# Sheet1.net
KiCad netlist of a schematic drawn in Altium Designer
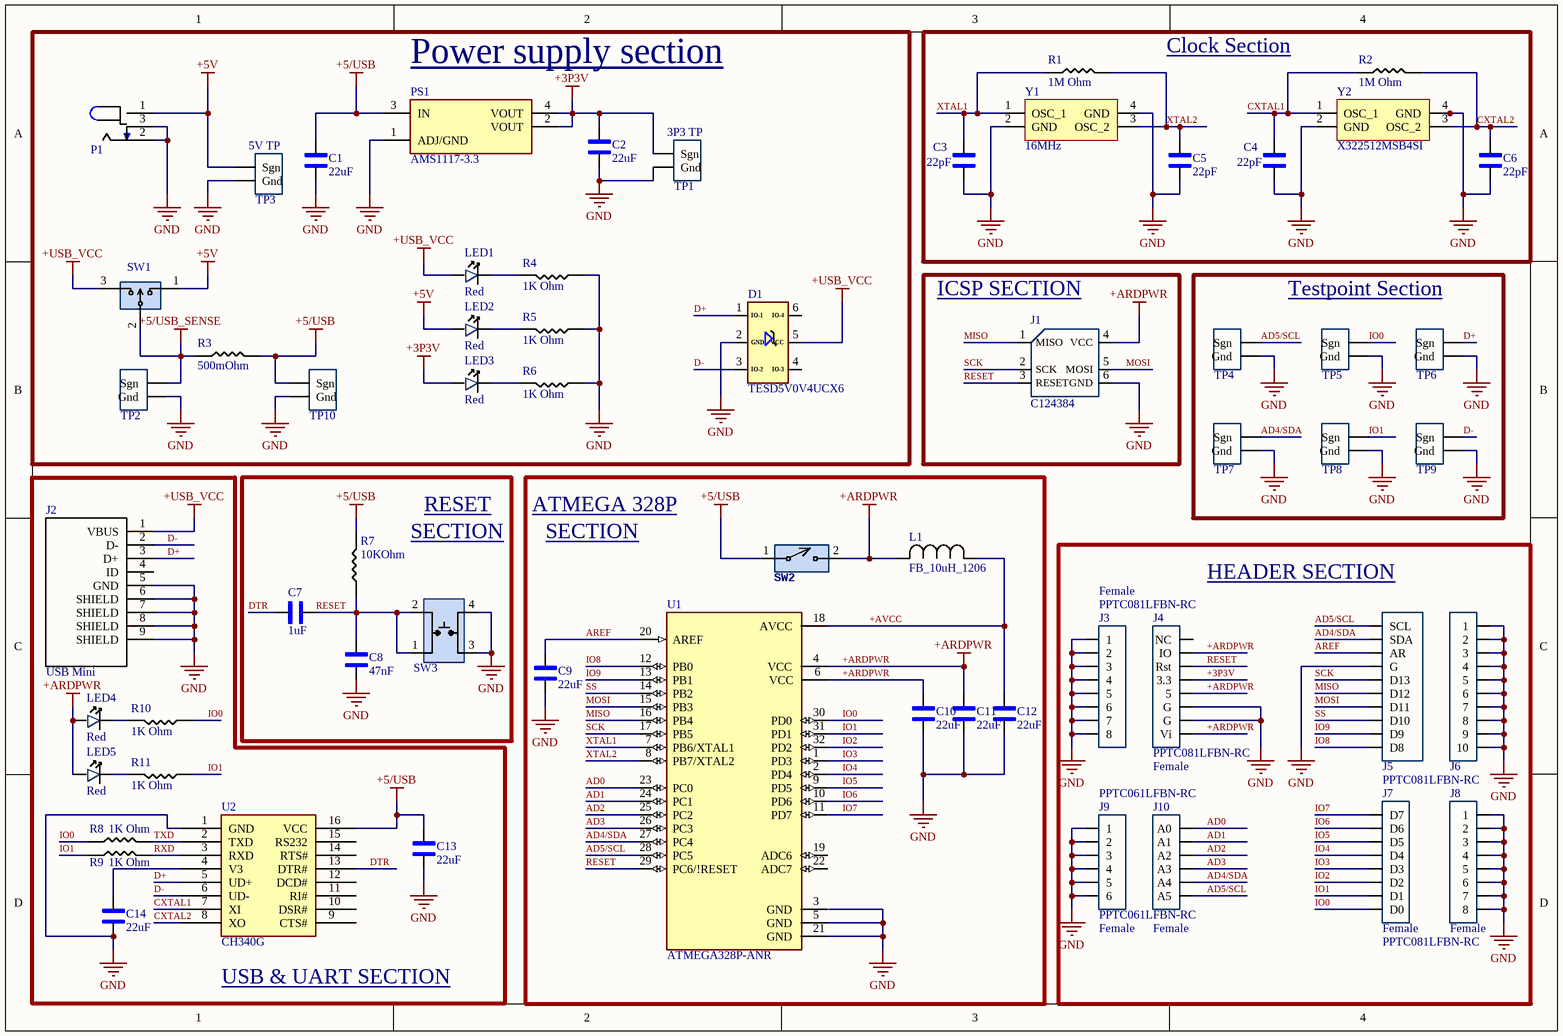
[diagram p0: Sheet1.SchDoc]

(export (version "E")
  (design (tool "Eeschema 10.0.6"))
  (components
    (comp (ref "C1")
      (value "22uF")
      (footprint "1206_Passive_Capacitor")
      (description "22uF ±10% 25V X5R 1206 Multilayer Ceramic Capacitors MLCC - SMD/SMT RoHS")
      (fields (field (name "MFR PART #") "CL31A226KAHNNNE") (field (name "LCSC PART#") "C12891"))
      (libsource (lib "ECEN5730Lib_2023_05_DS (1)") (part "C_22uF_1206"))
    )
    (comp (ref "C2")
      (value "22uF")
      (footprint "1206_Passive_Capacitor")
      (description "22uF ±10% 25V X5R 1206 Multilayer Ceramic Capacitors MLCC - SMD/SMT RoHS")
      (fields (field (name "MFR PART #") "CL31A226KAHNNNE") (field (name "LCSC PART#") "C12891"))
      (libsource (lib "ECEN5730Lib_2023_05_DS (1)") (part "C_22uF_1206"))
    )
    (comp (ref "C3")
      (value "22pF")
      (footprint "1206_Passive_Capacitor")
      (description "22pF ±5% 1kV C0G 1206 Multilayer Ceramic Capacitors MLCC - SMD/SMT RoHS")
      (fields (field (name "LCSC PART#") "C107174") (field (name "MFR PART #") "CC1206JKNPOCBN220"))
      (libsource (lib "ECEN5730Lib_2023_05_DS (1)") (part "C_22pF_1206"))
    )
    (comp (ref "C4")
      (value "22pF")
      (footprint "1206_Passive_Capacitor")
      (description "22pF ±5% 1kV C0G 1206 Multilayer Ceramic Capacitors MLCC - SMD/SMT RoHS")
      (fields (field (name "LCSC PART#") "C107174") (field (name "MFR PART #") "CC1206JKNPOCBN220"))
      (libsource (lib "ECEN5730Lib_2023_05_DS (1)") (part "C_22pF_1206"))
    )
    (comp (ref "C5")
      (value "22pF")
      (footprint "1206_Passive_Capacitor")
      (description "22pF ±5% 1kV C0G 1206 Multilayer Ceramic Capacitors MLCC - SMD/SMT RoHS")
      (fields (field (name "LCSC PART#") "C107174") (field (name "MFR PART #") "CC1206JKNPOCBN220"))
      (libsource (lib "ECEN5730Lib_2023_05_DS (1)") (part "C_22pF_1206"))
    )
    (comp (ref "C6")
      (value "22pF")
      (footprint "1206_Passive_Capacitor")
      (description "22pF ±5% 1kV C0G 1206 Multilayer Ceramic Capacitors MLCC - SMD/SMT RoHS")
      (fields (field (name "LCSC PART#") "C107174") (field (name "MFR PART #") "CC1206JKNPOCBN220"))
      (libsource (lib "ECEN5730Lib_2023_05_DS (1)") (part "C_22pF_1206"))
    )
    (comp (ref "C7")
      (value "1uF")
      (footprint "1206_Passive_Capacitor")
      (description "MULTILAYER CERAMIC CAPACITORS MLCC - SMD/SMT 1UF 50V 1206 ROHS")
      (fields (field (name "MFR PART #") "CL31B105KBHNNNE") (field (name "LCSC PART#") "C1848"))
      (libsource (lib "ECEN5730Lib_2023_05_DS (1)") (part "C_1uF_1206"))
    )
    (comp (ref "C8")
      (value "47nF")
      (footprint "1206_Passive_Capacitor")
      (description "47nF ±5% 50V C0G 1206 Multilayer Ceramic Capacitors MLCC - SMD/SMT RoHS")
      (fields (field (name "LCSC PART#") "C21812") (field (name "MFR PART #") "GRM31M5C1H473JA01L"))
      (libsource (lib "ECEN5730Lib_2023_05_DS (1)") (part "C_47nF_1206"))
    )
    (comp (ref "C9")
      (value "22uF")
      (footprint "1206_Passive_Capacitor")
      (description "22uF ±10% 25V X5R 1206 Multilayer Ceramic Capacitors MLCC - SMD/SMT RoHS")
      (fields (field (name "MFR PART #") "CL31A226KAHNNNE") (field (name "LCSC PART#") "C12891"))
      (libsource (lib "ECEN5730Lib_2023_05_DS (1)") (part "C_22uF_1206"))
    )
    (comp (ref "C10")
      (value "22uF")
      (footprint "1206_Passive_Capacitor")
      (description "22uF ±10% 25V X5R 1206 Multilayer Ceramic Capacitors MLCC - SMD/SMT RoHS")
      (fields (field (name "MFR PART #") "CL31A226KAHNNNE") (field (name "LCSC PART#") "C12891"))
      (libsource (lib "ECEN5730Lib_2023_05_DS (1)") (part "C_22uF_1206"))
    )
    (comp (ref "C11")
      (value "22uF")
      (footprint "1206_Passive_Capacitor")
      (description "22uF ±10% 25V X5R 1206 Multilayer Ceramic Capacitors MLCC - SMD/SMT RoHS")
      (fields (field (name "MFR PART #") "CL31A226KAHNNNE") (field (name "LCSC PART#") "C12891"))
      (libsource (lib "ECEN5730Lib_2023_05_DS (1)") (part "C_22uF_1206"))
    )
    (comp (ref "C12")
      (value "22uF")
      (footprint "1206_Passive_Capacitor")
      (description "22uF ±10% 25V X5R 1206 Multilayer Ceramic Capacitors MLCC - SMD/SMT RoHS")
      (fields (field (name "MFR PART #") "CL31A226KAHNNNE") (field (name "LCSC PART#") "C12891"))
      (libsource (lib "ECEN5730Lib_2023_05_DS (1)") (part "C_22uF_1206"))
    )
    (comp (ref "C13")
      (value "22uF")
      (footprint "1206_Passive_Capacitor")
      (description "22uF ±10% 25V X5R 1206 Multilayer Ceramic Capacitors MLCC - SMD/SMT RoHS")
      (fields (field (name "MFR PART #") "CL31A226KAHNNNE") (field (name "LCSC PART#") "C12891"))
      (libsource (lib "ECEN5730Lib_2023_05_DS (1)") (part "C_22uF_1206"))
    )
    (comp (ref "C14")
      (value "22uF")
      (footprint "1206_Passive_Capacitor")
      (description "22uF ±10% 25V X5R 1206 Multilayer Ceramic Capacitors MLCC - SMD/SMT RoHS")
      (fields (field (name "MFR PART #") "CL31A226KAHNNNE") (field (name "LCSC PART#") "C12891"))
      (libsource (lib "ECEN5730Lib_2023_05_DS (1)") (part "C_22uF_1206"))
    )
    (comp (ref "D1")
      (value "TESD5V0V4UCX6")
      (footprint "TVS - TESD")
      (description "TVS SOT-23 ROHS")
      (fields (field (name "LCSC PART#") "C5289077"))
      (libsource (lib "ECEN5730Lib_2023_05_DS_NEW") (part "D_TVS_Diode_TESD"))
    )
    (comp (ref "J1")
      (value "NRPN032PAEN-RC")
      (footprint "ICSP")
      (description "Connector Header Through Hole 6 position 0.079\" (2.00mm)")
      (fields (field (name "LCSC PART#") "C124384"))
      (libsource (lib "ECEN5730Lib_2023_05_DS (1)") (part "J_ICSP"))
    )
    (comp (ref "J2")
      (value "USB Mini")
      (footprint "USB_MINI_B")
      (description "Through Hole USB Connectors RoHS")
      (fields (field (name "LCSC PART#") "C46398") (field (name "MFR PART #") "920-462A2021D10102"))
      (libsource (lib "ECEN5730Lib_2023_05_DS (1)") (part "J_USB_B_Mini"))
    )
    (comp (ref "J3")
      (value "PPTC081LFBN-RC")
      (footprint "8_PIN_100MIL - Female")
      (description "8 Position Header Connector 0.100\" (2.54mm) Through Hole Tin")
      (fields (field (name "LCSC PART#") "C27438") (field (name "ALTIUM_VALUE") "Female"))
      (libsource (lib "") (part "JF_8_PIN_FEMALE_1"))
    )
    (comp (ref "J4")
      (value "PPTC081LFBN-RC")
      (footprint "8_PIN_ARD-PWR_100MIL")
      (description "8 Position Header Connector 0.100\" (2.54mm) Through Hole Tin")
      (fields (field (name "LCSC PART#") "C27438") (field (name "ALTIUM_VALUE") "Female"))
      (libsource (lib "ECEN5730Lib_2023_05_DS (1)") (part "JF_8_PIN_FEMA_ARD-Pwr"))
    )
    (comp (ref "J5")
      (value "PPTC101LFBN-RC")
      (footprint "10_PIN_ARDUINO_100MIL")
      (description "10 Position Header Connector 0.100\" (2.54mm) Through Hole Tin")
      (fields (field (name "LCSC PART#") "C225507"))
      (libsource (lib "ECEN5730Lib_2023_05_DS (1)") (part "JF_10_PIN_FEMA_ARDUINO"))
    )
    (comp (ref "J6")
      (value "PPTC101LFBN-RC")
      (footprint "10_PIN_100MIL - Female")
      (description "10 Position Header Connector 0.100\" (2.54mm) Through Hole Tin")
      (fields (field (name "LCSC PART#") "C225507"))
      (libsource (lib "ECEN5730Lib_2023_05_DS (1)") (part "JF_10_PIN_FEMALE_"))
    )
    (comp (ref "J7")
      (value "PPTC081LFBN-RC")
      (footprint "8_PIN_ARD-DIG_100MIL")
      (description "8 Position Header Connector 0.100\" (2.54mm) Through Hole Tin")
      (fields (field (name "LCSC PART#") "C27438") (field (name "ALTIUM_VALUE") "Female"))
      (libsource (lib "ECEN5730Lib_2023_05_DS (1)") (part "JF_8_PIN_FEMA_ARD-Dig"))
    )
    (comp (ref "J8")
      (value "PPTC081LFBN-RC")
      (footprint "8_PIN_100MIL - Female")
      (description "8 Position Header Connector 0.100\" (2.54mm) Through Hole Tin")
      (fields (field (name "LCSC PART#") "C27438") (field (name "ALTIUM_VALUE") "Female"))
      (libsource (lib "ECEN5730Lib_2023_05_DS (1)") (part "JF_8_PIN_FEMALE"))
    )
    (comp (ref "J9")
      (value "PPTC061LFBN-RC")
      (footprint "6_PIN_100MIL -Female")
      (description "6 Position Header Connector 0.100\" (2.54mm) Through Hole Tin")
      (fields (field (name "LCSC PART#") "C40877") (field (name "ALTIUM_VALUE") "Female"))
      (libsource (lib "ECEN5730Lib_2023_05_DS (1)") (part "JF_6_PIN_FEMALE"))
    )
    (comp (ref "J10")
      (value "PPTC061LFBN-RC")
      (footprint "6_PIN_ARD-Analog_100mil")
      (description "6 Position Header Connector 0.100\" (2.54mm) Through Hole Tin")
      (fields (field (name "LCSC PART#") "C40877") (field (name "ALTIUM_VALUE") "Female"))
      (libsource (lib "ECEN5730Lib_2023_05_DS (1)") (part "JF_6_PIN_FEMA_ARD-Anolog"))
    )
    (comp (ref "L1")
      (value "FB_10uH_1206")
      (footprint "AIML-1206_ABR-M")
      (description "25mA 10uH ±10% 800mΩ 1206  Inductors (SMD) ROHS")
      (fields (field (name "MFR PART #") "CMI321609X100KT") (field (name "LCSC PART#") "C1051"))
      (libsource (lib "ECEN5730Lib_2023_05_DS (1)") (part "FB_10uH_1206"))
    )
    (comp (ref "LED1")
      (value "Red")
      (footprint "LED_1206")
      (description "Red 621~631nm 1206 Light Emitting Diodes (LED) RoHS")
      (fields (field (name "MFR PART #") "15-21/R6C-FQ1R1B/2T") (field (name "LCSC PART#") "C93133"))
      (libsource (lib "ECEN5730Lib_2023_05_DS (1)") (part "LED_RED_1206"))
    )
    (comp (ref "LED2")
      (value "Red")
      (footprint "LED_1206")
      (description "Red 621~631nm 1206 Light Emitting Diodes (LED) RoHS")
      (fields (field (name "MFR PART #") "15-21/R6C-FQ1R1B/2T") (field (name "LCSC PART#") "C93133"))
      (libsource (lib "ECEN5730Lib_2023_05_DS (1)") (part "LED_RED_1206"))
    )
    (comp (ref "LED3")
      (value "Red")
      (footprint "LED_1206")
      (description "Red 621~631nm 1206 Light Emitting Diodes (LED) RoHS")
      (fields (field (name "MFR PART #") "15-21/R6C-FQ1R1B/2T") (field (name "LCSC PART#") "C93133"))
      (libsource (lib "ECEN5730Lib_2023_05_DS (1)") (part "LED_RED_1206"))
    )
    (comp (ref "LED4")
      (value "Red")
      (footprint "LED_1206")
      (description "Red 621~631nm 1206 Light Emitting Diodes (LED) RoHS")
      (fields (field (name "MFR PART #") "15-21/R6C-FQ1R1B/2T") (field (name "LCSC PART#") "C93133"))
      (libsource (lib "ECEN5730Lib_2023_05_DS (1)") (part "LED_RED_1206"))
    )
    (comp (ref "LED5")
      (value "Red")
      (footprint "LED_1206")
      (description "Red 621~631nm 1206 Light Emitting Diodes (LED) RoHS")
      (fields (field (name "MFR PART #") "15-21/R6C-FQ1R1B/2T") (field (name "LCSC PART#") "C93133"))
      (libsource (lib "ECEN5730Lib_2023_05_DS (1)") (part "LED_RED_1206"))
    )
    (comp (ref "P1")
      (value "Power Jack")
      (footprint "Power_Jack")
      (description "Power Barrel Connector Jack 2.10mm ID (0.083\"), 5.50mm OD (0.217\") Through Hole, Right Angle")
      (fields (field (name "MFR PART #") "PJ-102A") (field (name "LCSC PART#") "C136744"))
      (libsource (lib "ECEN5730Lib_2023_05_DS (1)") (part "P_Power Jack"))
    )
    (comp (ref "PS1")
      (value "AMS1117-3.3")
      (footprint "LDO")
      (description "LOW DROPOUT REGULATORS(LDO) POSITIVE FIXED 1.3V @ 800MA 15V 3.3V 1A SOT-223 ROHS")
      (fields (field (name "LCSC PART#") "C6186"))
      (libsource (lib "ECEN5730Lib_2023_05_DS (1)") (part "PS_AMS_LDO_3v3"))
    )
    (comp (ref "R1")
      (value "1M Ohm")
      (footprint "1206_Passive_Resitor")
      (description "CHIP RESISTOR - SURFACE MOUNT 1MOHMS ±1% 1/4W 1206 ROHS")
      (fields (field (name "MFR PART #") "RMCF1206JT1M00") (field (name "LCSC PART#") "C17927"))
      (libsource (lib "ECEN5730Lib_2023_05_DS (1)") (part "R_1M_1206"))
    )
    (comp (ref "R2")
      (value "1M Ohm")
      (footprint "1206_Passive_Resitor")
      (description "CHIP RESISTOR - SURFACE MOUNT 1MOHMS ±1% 1/4W 1206 ROHS")
      (fields (field (name "MFR PART #") "RMCF1206JT1M00") (field (name "LCSC PART#") "C17927"))
      (libsource (lib "ECEN5730Lib_2023_05_DS (1)") (part "R_1M_1206"))
    )
    (comp (ref "R3")
      (value "500mOhm")
      (footprint "1206_Passive_Resitor")
      (description "Resistors/Shunt 250mW 500mΩ ±800ppm/℃ ±5% 1206  Current Sense  Resistors ROHS")
      (fields (field (name "MFR PART #") "1206W4J050KT5E") (field (name "LCSC PART#") "C247433"))
      (libsource (lib "ECEN5730Lib_2023_05_DS (1)") (part "R_500mOhm_1206"))
    )
    (comp (ref "R4")
      (value "1K Ohm")
      (footprint "1206_Passive_Resitor")
      (description "CHIP RESISTOR - SURFACE MOUNT 1KOHMS ±1% 1/4W 1206 ROHS")
      (fields (field (name "MFR PART #") "RNCP1206FTD1K00CT") (field (name "LCSC PART#") "C4410"))
      (libsource (lib "ECEN5730Lib_2023_05_DS (1)") (part "R_1K_1206"))
    )
    (comp (ref "R5")
      (value "1K Ohm")
      (footprint "1206_Passive_Resitor")
      (description "CHIP RESISTOR - SURFACE MOUNT 1KOHMS ±1% 1/4W 1206 ROHS")
      (fields (field (name "MFR PART #") "RNCP1206FTD1K00CT") (field (name "LCSC PART#") "C4410"))
      (libsource (lib "ECEN5730Lib_2023_05_DS (1)") (part "R_1K_1206"))
    )
    (comp (ref "R6")
      (value "1K Ohm")
      (footprint "1206_Passive_Resitor")
      (description "CHIP RESISTOR - SURFACE MOUNT 1KOHMS ±1% 1/4W 1206 ROHS")
      (fields (field (name "MFR PART #") "RNCP1206FTD1K00CT") (field (name "LCSC PART#") "C4410"))
      (libsource (lib "ECEN5730Lib_2023_05_DS (1)") (part "R_1K_1206"))
    )
    (comp (ref "R7")
      (value "10KOhm")
      (footprint "1206_Passive_Resitor")
      (description "10 kOhms ±5% 0.25W, 1/4W Chip Resistor 1206 (3216 Metric) Automotive AEC-Q200 Thick Film")
      (fields (field (name "MFR PART #") "RMCF1206FT10K0") (field (name "LCSC PART#") "C17902"))
      (libsource (lib "ECEN5730Lib_2023_05_DS (1)") (part "R_10KOhm_1206"))
    )
    (comp (ref "R8")
      (value "1K Ohm")
      (footprint "1206_Passive_Resitor")
      (description "CHIP RESISTOR - SURFACE MOUNT 1KOHMS ±1% 1/4W 1206 ROHS")
      (fields (field (name "MFR PART #") "RNCP1206FTD1K00CT") (field (name "LCSC PART#") "C4410"))
      (libsource (lib "ECEN5730Lib_2023_05_DS (1)") (part "R_1K_1206"))
    )
    (comp (ref "R9")
      (value "1K Ohm")
      (footprint "1206_Passive_Resitor")
      (description "CHIP RESISTOR - SURFACE MOUNT 1KOHMS ±1% 1/4W 1206 ROHS")
      (fields (field (name "MFR PART #") "RNCP1206FTD1K00CT") (field (name "LCSC PART#") "C4410"))
      (libsource (lib "ECEN5730Lib_2023_05_DS (1)") (part "R_1K_1206"))
    )
    (comp (ref "R10")
      (value "1K Ohm")
      (footprint "1206_Passive_Resitor")
      (description "CHIP RESISTOR - SURFACE MOUNT 1KOHMS ±1% 1/4W 1206 ROHS")
      (fields (field (name "MFR PART #") "RNCP1206FTD1K00CT") (field (name "LCSC PART#") "C4410"))
      (libsource (lib "ECEN5730Lib_2023_05_DS (1)") (part "R_1K_1206"))
    )
    (comp (ref "R11")
      (value "1K Ohm")
      (footprint "1206_Passive_Resitor")
      (description "CHIP RESISTOR - SURFACE MOUNT 1KOHMS ±1% 1/4W 1206 ROHS")
      (fields (field (name "MFR PART #") "RNCP1206FTD1K00CT") (field (name "LCSC PART#") "C4410"))
      (libsource (lib "ECEN5730Lib_2023_05_DS (1)") (part "R_1K_1206"))
    )
    (comp (ref "SW1")
      (value "PREC003SAAN-RC")
      (footprint "3_PIN_100mil")
      (description "Connector Header Through Hole 3 position 0.100\" (2.54mm)")
      (fields (field (name "LCSC PART#") "C49257"))
      (libsource (lib "ECEN5730Lib_2023_05_DS (1)") (part "SW_3Pin_100mil_Switch"))
    )
    (comp (ref "SW2")
      (value "SW_2Pin_100mil_Switch")
      (footprint "2Pin-Header-Conn")
      (description "2Pin Header")
      (fields (field (name "LCSC PART#") "C124375"))
      (libsource (lib "ECEN5730Lib_2023_05_DS (1)") (part "SW_2Pin_100mil_Switch"))
    )
    (comp (ref "SW3")
      (value "TL3305AF160QG")
      (footprint "Switch_JLC")
      (description "Tactile Switch SPST-NO Top Actuated Surface Mount")
      (fields (field (name "MFR PART #") "KH-4.5X4.5X4.3H-STM") (field (name "LCSC PART#") "C2837550"))
      (libsource (lib "ECEN5730Lib_2023_05_DS (1)") (part "SW_Push_Button_JLC"))
    )
    (comp (ref "TP1")
      (value "10x Probe TP")
      (footprint "TP10x_Probe")
      (description "Test Point 300 mil centers")
      (libsource (lib "ECEN5730Lib_2023_05_DS (1)") (part "TP_10x_Probe"))
    )
    (comp (ref "TP2")
      (value "10x Probe TP")
      (footprint "TP10x_Probe")
      (description "Test Point 300 mil centers")
      (libsource (lib "") (part "TP_10x_Probe_1"))
    )
    (comp (ref "TP3")
      (value "10x Probe TP")
      (footprint "TP10x_Probe")
      (description "Test Point 300 mil centers")
      (libsource (lib "ECEN5730Lib_2023_05_DS (1)") (part "TP_10x_Probe"))
    )
    (comp (ref "TP4")
      (value "10x Probe TP")
      (footprint "TP10x_Probe")
      (description "Test Point 300 mil centers")
      (libsource (lib "") (part "TP_10x_Probe_1"))
    )
    (comp (ref "TP5")
      (value "10x Probe TP")
      (footprint "TP10x_Probe")
      (description "Test Point 300 mil centers")
      (libsource (lib "") (part "TP_10x_Probe_1"))
    )
    (comp (ref "TP6")
      (value "10x Probe TP")
      (footprint "TP10x_Probe")
      (description "Test Point 300 mil centers")
      (libsource (lib "") (part "TP_10x_Probe_1"))
    )
    (comp (ref "TP7")
      (value "10x Probe TP")
      (footprint "TP10x_Probe")
      (description "Test Point 300 mil centers")
      (libsource (lib "") (part "TP_10x_Probe_1"))
    )
    (comp (ref "TP8")
      (value "10x Probe TP")
      (footprint "TP10x_Probe")
      (description "Test Point 300 mil centers")
      (libsource (lib "") (part "TP_10x_Probe_1"))
    )
    (comp (ref "TP9")
      (value "10x Probe TP")
      (footprint "TP10x_Probe")
      (description "Test Point 300 mil centers")
      (libsource (lib "") (part "TP_10x_Probe_1"))
    )
    (comp (ref "TP10")
      (value "10x Probe TP")
      (footprint "TP10x_Probe")
      (description "Test Point 300 mil centers")
      (libsource (lib "ECEN5730Lib_2023_05_DS (1)") (part "TP_10x_Probe"))
    )
    (comp (ref "U1")
      (value "ATMEGA328P-ANR")
      (footprint "ATMega328P")
      (description "AVR AVR® ATmega Microcontroller IC 8-Bit 20MHz 32KB (16K x 16) FLASH 32-TQFP (7x7)")
      (fields (field (name "MFR PART #") "ATMEGA328P-AU") (field (name "LCSC PART#") "C14877"))
      (libsource (lib "ECEN5730Lib_2023_05_DS (1)") (part "U_ATMega328P"))
    )
    (comp (ref "U2")
      (value "CH340G")
      (footprint "USB to serial")
      (description "Transceiver USB 2.0 2Mbps SOP-16_150mil USB ICs RoHS")
      (fields (field (name "LCSC PART#") "C14267"))
      (libsource (lib "ECEN5730Lib_2023_05_DS (1)") (part "U_USBtoSerial"))
    )
    (comp (ref "Y1")
      (value "16MHz")
      (footprint "Crystal resonator")
      (description "±10ppm 16000000Hz -40℃~85℃ 贴片无源晶振 60Ω 9pF SMD3225-4P Crystals ROHS")
      (fields (field (name "LCSC PART#") "C13738") (field (name "MFR PART #") "X322516MLB4SI"))
      (libsource (lib "ECEN5730Lib_2023_05_DS (1)") (part "X_16Mhz_Res"))
    )
    (comp (ref "Y2")
      (value "X322512MSB4SI")
      (footprint "Crystal resonator")
      (description "SMD Crystal Resonators 12MHz ±10ppm SMD-3225_4P RoHS")
      (fields (field (name "LCSC PART#") "C9002"))
      (libsource (lib "ECEN5730Lib_2023_05_DS (1)") (part "X_12MHz_Res"))
    )
  )
  (nets
    (net (code "1") (name "+3P3V") (class "Default")
      (node (ref "C2") (pin "2") (pinfunction "2_2") (pintype "passive"))
      (node (ref "J4") (pin "4") (pinfunction "3.3_4") (pintype "passive"))
      (node (ref "LED3") (pin "1") (pinfunction "1_1") (pintype "passive"))
      (node (ref "PS1") (pin "2") (pinfunction "VOUT_2") (pintype "power_in"))
      (node (ref "PS1") (pin "4") (pinfunction "VOUT_4") (pintype "power_in"))
      (node (ref "TP1") (pin "1") (pinfunction "Sgn_1") (pintype "passive"))
    )
    (net (code "2") (name "+5V") (class "Default")
      (node (ref "LED2") (pin "1") (pinfunction "1_1") (pintype "passive"))
      (node (ref "P1") (pin "1") (pinfunction "1_1") (pintype "power_in"))
      (node (ref "SW1") (pin "1") (pinfunction "1_1") (pintype "passive"))
      (node (ref "TP3") (pin "1") (pinfunction "Sgn_1") (pintype "passive"))
    )
    (net (code "3") (name "+5{slash}USB") (class "Default")
      (node (ref "C1") (pin "2") (pinfunction "2_2") (pintype "passive"))
      (node (ref "C13") (pin "2") (pinfunction "2_2") (pintype "passive"))
      (node (ref "PS1") (pin "3") (pinfunction "IN_3") (pintype "power_in"))
      (node (ref "R3") (pin "2") (pinfunction "2_2") (pintype "passive"))
      (node (ref "R7") (pin "2") (pinfunction "2_2") (pintype "passive"))
      (node (ref "SW2") (pin "1") (pinfunction "1_1") (pintype "passive"))
      (node (ref "TP10") (pin "1") (pinfunction "Sgn_1") (pintype "passive"))
      (node (ref "U2") (pin "16") (pinfunction "VCC_16") (pintype "passive"))
    )
    (net (code "4") (name "+5{slash}USB_SENSE") (class "Default")
      (node (ref "R3") (pin "1") (pinfunction "1_1") (pintype "passive"))
      (node (ref "SW1") (pin "2") (pinfunction "2_2") (pintype "passive"))
      (node (ref "TP2") (pin "1") (pinfunction "Sgn_1") (pintype "passive"))
    )
    (net (code "5") (name "+ARDPWR") (class "Default")
      (node (ref "C10") (pin "2") (pinfunction "2_2") (pintype "passive"))
      (node (ref "C11") (pin "2") (pinfunction "2_2") (pintype "passive"))
      (node (ref "J1") (pin "4") (pinfunction "VCC_4") (pintype "passive"))
      (node (ref "J4") (pin "2") (pinfunction "IO_2") (pintype "passive"))
      (node (ref "J4") (pin "5") (pinfunction "5_5") (pintype "passive"))
      (node (ref "J4") (pin "8") (pinfunction "Vi_8") (pintype "passive"))
      (node (ref "L1") (pin "2") (pinfunction "2_2") (pintype "passive"))
      (node (ref "LED4") (pin "1") (pinfunction "1_1") (pintype "passive"))
      (node (ref "LED5") (pin "1") (pinfunction "1_1") (pintype "passive"))
      (node (ref "SW2") (pin "2") (pinfunction "2_2") (pintype "passive"))
      (node (ref "U1") (pin "4") (pinfunction "VCC_4") (pintype "power_in"))
      (node (ref "U1") (pin "6") (pinfunction "VCC_6") (pintype "power_in"))
    )
    (net (code "6") (name "+USB_VCC") (class "Default")
      (node (ref "D1") (pin "5") (pinfunction "VCC_5") (pintype "passive"))
      (node (ref "J2") (pin "1") (pinfunction "VBUS_1") (pintype "passive"))
      (node (ref "LED1") (pin "1") (pinfunction "1_1") (pintype "passive"))
      (node (ref "SW1") (pin "3") (pinfunction "3_3") (pintype "passive"))
    )
    (net (code "7") (name "/+AVCC") (class "Default")
      (node (ref "C12") (pin "2") (pinfunction "2_2") (pintype "passive"))
      (node (ref "L1") (pin "1") (pinfunction "1_1") (pintype "passive"))
      (node (ref "U1") (pin "18") (pinfunction "AVCC_18") (pintype "power_in"))
    )
    (net (code "8") (name "/AD0") (class "Default")
      (node (ref "J10") (pin "1") (pinfunction "A0_1") (pintype "passive"))
      (node (ref "U1") (pin "23") (pinfunction "PC0_23") (pintype "bidirectional"))
    )
    (net (code "9") (name "/AD1") (class "Default")
      (node (ref "J10") (pin "2") (pinfunction "A1_2") (pintype "passive"))
      (node (ref "U1") (pin "24") (pinfunction "PC1_24") (pintype "bidirectional"))
    )
    (net (code "10") (name "/AD2") (class "Default")
      (node (ref "J10") (pin "3") (pinfunction "A2_3") (pintype "passive"))
      (node (ref "U1") (pin "25") (pinfunction "PC2_25") (pintype "bidirectional"))
    )
    (net (code "11") (name "/AD3") (class "Default")
      (node (ref "J10") (pin "4") (pinfunction "A3_4") (pintype "passive"))
      (node (ref "U1") (pin "26") (pinfunction "PC3_26") (pintype "bidirectional"))
    )
    (net (code "12") (name "/AD4{slash}SDA") (class "Default")
      (node (ref "J10") (pin "5") (pinfunction "A4_5") (pintype "passive"))
      (node (ref "J5") (pin "2") (pinfunction "SDA_2") (pintype "passive"))
      (node (ref "TP7") (pin "1") (pinfunction "Sgn_1") (pintype "passive"))
      (node (ref "U1") (pin "27") (pinfunction "PC4_27") (pintype "bidirectional"))
    )
    (net (code "13") (name "/AD5{slash}SCL") (class "Default")
      (node (ref "J10") (pin "6") (pinfunction "A5_6") (pintype "passive"))
      (node (ref "J5") (pin "1") (pinfunction "SCL_1") (pintype "passive"))
      (node (ref "TP4") (pin "1") (pinfunction "Sgn_1") (pintype "passive"))
      (node (ref "U1") (pin "28") (pinfunction "PC5_28") (pintype "bidirectional"))
    )
    (net (code "14") (name "/AREF") (class "Default")
      (node (ref "C9") (pin "2") (pinfunction "2_2") (pintype "passive"))
      (node (ref "J5") (pin "3") (pinfunction "AR_3") (pintype "passive"))
      (node (ref "U1") (pin "20") (pinfunction "AREF_20") (pintype "input"))
    )
    (net (code "15") (name "/CXTAL1") (class "Default")
      (node (ref "C4") (pin "2") (pinfunction "2_2") (pintype "passive"))
      (node (ref "R2") (pin "1") (pinfunction "1_1") (pintype "passive"))
      (node (ref "U2") (pin "7") (pinfunction "XI_7") (pintype "passive"))
      (node (ref "Y2") (pin "1") (pinfunction "OSC_1_1") (pintype "passive"))
    )
    (net (code "16") (name "/CXTAL2") (class "Default")
      (node (ref "C6") (pin "2") (pinfunction "2_2") (pintype "passive"))
      (node (ref "R2") (pin "2") (pinfunction "2_2") (pintype "passive"))
      (node (ref "U2") (pin "8") (pinfunction "XO_8") (pintype "passive"))
      (node (ref "Y2") (pin "3") (pinfunction "OSC_2_3") (pintype "passive"))
    )
    (net (code "17") (name "/D+") (class "Default")
      (node (ref "D1") (pin "1") (pinfunction "IO-1_1") (pintype "passive"))
      (node (ref "J2") (pin "3") (pinfunction "D+_3") (pintype "passive"))
      (node (ref "TP6") (pin "1") (pinfunction "Sgn_1") (pintype "passive"))
      (node (ref "U2") (pin "5") (pinfunction "UD+_5") (pintype "passive"))
    )
    (net (code "18") (name "/D-") (class "Default")
      (node (ref "D1") (pin "3") (pinfunction "IO-2_3") (pintype "passive"))
      (node (ref "J2") (pin "2") (pinfunction "D-_2") (pintype "passive"))
      (node (ref "TP9") (pin "1") (pinfunction "Sgn_1") (pintype "passive"))
      (node (ref "U2") (pin "6") (pinfunction "UD-_6") (pintype "passive"))
    )
    (net (code "19") (name "/DTR") (class "Default")
      (node (ref "C7") (pin "2") (pinfunction "2_2") (pintype "passive"))
      (node (ref "U2") (pin "13") (pinfunction "DTR#_13") (pintype "passive"))
    )
    (net (code "20") (name "/IO0") (class "Default")
      (node (ref "J7") (pin "8") (pinfunction "D0_8") (pintype "passive"))
      (node (ref "R10") (pin "1") (pinfunction "1_1") (pintype "passive"))
      (node (ref "R8") (pin "1") (pinfunction "1_1") (pintype "passive"))
      (node (ref "TP5") (pin "1") (pinfunction "Sgn_1") (pintype "passive"))
      (node (ref "U1") (pin "30") (pinfunction "PD0_30") (pintype "bidirectional"))
    )
    (net (code "21") (name "/IO1") (class "Default")
      (node (ref "J7") (pin "7") (pinfunction "D1_7") (pintype "passive"))
      (node (ref "R11") (pin "1") (pinfunction "1_1") (pintype "passive"))
      (node (ref "R9") (pin "1") (pinfunction "1_1") (pintype "passive"))
      (node (ref "TP8") (pin "1") (pinfunction "Sgn_1") (pintype "passive"))
      (node (ref "U1") (pin "31") (pinfunction "PD1_31") (pintype "bidirectional"))
    )
    (net (code "22") (name "/IO2") (class "Default")
      (node (ref "J7") (pin "6") (pinfunction "D2_6") (pintype "passive"))
      (node (ref "U1") (pin "32") (pinfunction "PD2_32") (pintype "bidirectional"))
    )
    (net (code "23") (name "/IO3") (class "Default")
      (node (ref "J7") (pin "5") (pinfunction "D3_5") (pintype "passive"))
      (node (ref "U1") (pin "1") (pinfunction "PD3_1") (pintype "bidirectional"))
    )
    (net (code "24") (name "/IO4") (class "Default")
      (node (ref "J7") (pin "4") (pinfunction "D4_4") (pintype "passive"))
      (node (ref "U1") (pin "2") (pinfunction "PD4_2") (pintype "bidirectional"))
    )
    (net (code "25") (name "/IO5") (class "Default")
      (node (ref "J7") (pin "3") (pinfunction "D5_3") (pintype "passive"))
      (node (ref "U1") (pin "9") (pinfunction "PD5_9") (pintype "bidirectional"))
    )
    (net (code "26") (name "/IO6") (class "Default")
      (node (ref "J7") (pin "2") (pinfunction "D6_2") (pintype "passive"))
      (node (ref "U1") (pin "10") (pinfunction "PD6_10") (pintype "bidirectional"))
    )
    (net (code "27") (name "/IO7") (class "Default")
      (node (ref "J7") (pin "1") (pinfunction "D7_1") (pintype "passive"))
      (node (ref "U1") (pin "11") (pinfunction "PD7_11") (pintype "bidirectional"))
    )
    (net (code "28") (name "/IO8") (class "Default")
      (node (ref "J5") (pin "10") (pinfunction "D8_10") (pintype "passive"))
      (node (ref "U1") (pin "12") (pinfunction "PB0_12") (pintype "bidirectional"))
    )
    (net (code "29") (name "/IO9") (class "Default")
      (node (ref "J5") (pin "9") (pinfunction "D9_9") (pintype "passive"))
      (node (ref "U1") (pin "13") (pinfunction "PB1_13") (pintype "bidirectional"))
    )
    (net (code "30") (name "/MISO") (class "Default")
      (node (ref "J1") (pin "1") (pinfunction "MISO_1") (pintype "passive"))
      (node (ref "J5") (pin "6") (pinfunction "D12_6") (pintype "passive"))
      (node (ref "U1") (pin "16") (pinfunction "PB4_16") (pintype "bidirectional"))
    )
    (net (code "31") (name "/MOSI") (class "Default")
      (node (ref "J1") (pin "5") (pinfunction "MOSI_5") (pintype "passive"))
      (node (ref "J5") (pin "7") (pinfunction "D11_7") (pintype "passive"))
      (node (ref "U1") (pin "15") (pinfunction "PB3_15") (pintype "bidirectional"))
    )
    (net (code "32") (name "/RESET") (class "Default")
      (node (ref "C7") (pin "1") (pinfunction "1_1") (pintype "passive"))
      (node (ref "C8") (pin "2") (pinfunction "2_2") (pintype "passive"))
      (node (ref "J1") (pin "3") (pinfunction "RESET_3") (pintype "passive"))
      (node (ref "J4") (pin "3") (pinfunction "Rst_3") (pintype "passive"))
      (node (ref "R7") (pin "1") (pinfunction "1_1") (pintype "passive"))
      (node (ref "SW3") (pin "1") (pinfunction "1_1") (pintype "passive"))
      (node (ref "SW3") (pin "2") (pinfunction "2_2") (pintype "passive"))
      (node (ref "U1") (pin "29") (pinfunction "PC6/!RESET_29") (pintype "bidirectional"))
    )
    (net (code "33") (name "/RXD") (class "Default")
      (node (ref "R9") (pin "2") (pinfunction "2_2") (pintype "passive"))
      (node (ref "U2") (pin "3") (pinfunction "RXD_3") (pintype "passive"))
    )
    (net (code "34") (name "/SCK") (class "Default")
      (node (ref "J1") (pin "2") (pinfunction "SCK_2") (pintype "passive"))
      (node (ref "J5") (pin "5") (pinfunction "D13_5") (pintype "passive"))
      (node (ref "U1") (pin "17") (pinfunction "PB5_17") (pintype "bidirectional"))
    )
    (net (code "35") (name "/SS") (class "Default")
      (node (ref "J5") (pin "8") (pinfunction "D10_8") (pintype "passive"))
      (node (ref "U1") (pin "14") (pinfunction "PB2_14") (pintype "bidirectional"))
    )
    (net (code "36") (name "/TXD") (class "Default")
      (node (ref "R8") (pin "2") (pinfunction "2_2") (pintype "passive"))
      (node (ref "U2") (pin "2") (pinfunction "TXD_2") (pintype "passive"))
    )
    (net (code "37") (name "/XTAL1") (class "Default")
      (node (ref "C3") (pin "2") (pinfunction "2_2") (pintype "passive"))
      (node (ref "R1") (pin "1") (pinfunction "1_1") (pintype "passive"))
      (node (ref "U1") (pin "7") (pinfunction "PB6/XTAL1_7") (pintype "bidirectional"))
      (node (ref "Y1") (pin "1") (pinfunction "OSC_1_1") (pintype "passive"))
    )
    (net (code "38") (name "/XTAL2") (class "Default")
      (node (ref "C5") (pin "2") (pinfunction "2_2") (pintype "passive"))
      (node (ref "R1") (pin "2") (pinfunction "2_2") (pintype "passive"))
      (node (ref "U1") (pin "8") (pinfunction "PB7/XTAL2_8") (pintype "bidirectional"))
      (node (ref "Y1") (pin "3") (pinfunction "OSC_2_3") (pintype "passive"))
    )
    (net (code "39") (name "GND") (class "Default")
      (node (ref "C1") (pin "1") (pinfunction "1_1") (pintype "passive"))
      (node (ref "C10") (pin "1") (pinfunction "1_1") (pintype "passive"))
      (node (ref "C11") (pin "1") (pinfunction "1_1") (pintype "passive"))
      (node (ref "C12") (pin "1") (pinfunction "1_1") (pintype "passive"))
      (node (ref "C13") (pin "1") (pinfunction "1_1") (pintype "passive"))
      (node (ref "C14") (pin "1") (pinfunction "1_1") (pintype "passive"))
      (node (ref "C2") (pin "1") (pinfunction "1_1") (pintype "passive"))
      (node (ref "C3") (pin "1") (pinfunction "1_1") (pintype "passive"))
      (node (ref "C4") (pin "1") (pinfunction "1_1") (pintype "passive"))
      (node (ref "C5") (pin "1") (pinfunction "1_1") (pintype "passive"))
      (node (ref "C6") (pin "1") (pinfunction "1_1") (pintype "passive"))
      (node (ref "C8") (pin "1") (pinfunction "1_1") (pintype "passive"))
      (node (ref "C9") (pin "1") (pinfunction "1_1") (pintype "passive"))
      (node (ref "D1") (pin "2") (pinfunction "GND_2") (pintype "passive"))
      (node (ref "J1") (pin "6") (pinfunction "GND_6") (pintype "passive"))
      (node (ref "J2") (pin "5") (pinfunction "GND_5") (pintype "passive"))
      (node (ref "J2") (pin "6") (pinfunction "SHIELD_6") (pintype "passive"))
      (node (ref "J2") (pin "7") (pinfunction "SHIELD_7") (pintype "passive"))
      (node (ref "J2") (pin "8") (pinfunction "SHIELD_8") (pintype "passive"))
      (node (ref "J2") (pin "9") (pinfunction "SHIELD_9") (pintype "passive"))
      (node (ref "J3") (pin "1") (pinfunction "1_1") (pintype "passive"))
      (node (ref "J3") (pin "2") (pinfunction "2_2") (pintype "passive"))
      (node (ref "J3") (pin "3") (pinfunction "3_3") (pintype "passive"))
      (node (ref "J3") (pin "4") (pinfunction "4_4") (pintype "passive"))
      (node (ref "J3") (pin "5") (pinfunction "5_5") (pintype "passive"))
      (node (ref "J3") (pin "6") (pinfunction "6_6") (pintype "passive"))
      (node (ref "J3") (pin "7") (pinfunction "7_7") (pintype "passive"))
      (node (ref "J3") (pin "8") (pinfunction "8_8") (pintype "passive"))
      (node (ref "J4") (pin "6") (pinfunction "G_6") (pintype "passive"))
      (node (ref "J4") (pin "7") (pinfunction "G_7") (pintype "passive"))
      (node (ref "J5") (pin "4") (pinfunction "G_4") (pintype "passive"))
      (node (ref "J6") (pin "1") (pinfunction "1_1") (pintype "passive"))
      (node (ref "J6") (pin "10") (pinfunction "10_10") (pintype "passive"))
      (node (ref "J6") (pin "2") (pinfunction "2_2") (pintype "passive"))
      (node (ref "J6") (pin "3") (pinfunction "3_3") (pintype "passive"))
      (node (ref "J6") (pin "4") (pinfunction "4_4") (pintype "passive"))
      (node (ref "J6") (pin "5") (pinfunction "5_5") (pintype "passive"))
      (node (ref "J6") (pin "6") (pinfunction "6_6") (pintype "passive"))
      (node (ref "J6") (pin "7") (pinfunction "7_7") (pintype "passive"))
      (node (ref "J6") (pin "8") (pinfunction "8_8") (pintype "passive"))
      (node (ref "J6") (pin "9") (pinfunction "9_9") (pintype "passive"))
      (node (ref "J8") (pin "1") (pinfunction "1_1") (pintype "passive"))
      (node (ref "J8") (pin "2") (pinfunction "2_2") (pintype "passive"))
      (node (ref "J8") (pin "3") (pinfunction "3_3") (pintype "passive"))
      (node (ref "J8") (pin "4") (pinfunction "4_4") (pintype "passive"))
      (node (ref "J8") (pin "5") (pinfunction "5_5") (pintype "passive"))
      (node (ref "J8") (pin "6") (pinfunction "6_6") (pintype "passive"))
      (node (ref "J8") (pin "7") (pinfunction "7_7") (pintype "passive"))
      (node (ref "J8") (pin "8") (pinfunction "8_8") (pintype "passive"))
      (node (ref "J9") (pin "1") (pinfunction "1_1") (pintype "passive"))
      (node (ref "J9") (pin "2") (pinfunction "2_2") (pintype "passive"))
      (node (ref "J9") (pin "3") (pinfunction "3_3") (pintype "passive"))
      (node (ref "J9") (pin "4") (pinfunction "4_4") (pintype "passive"))
      (node (ref "J9") (pin "5") (pinfunction "5_5") (pintype "passive"))
      (node (ref "J9") (pin "6") (pinfunction "6_6") (pintype "passive"))
      (node (ref "P1") (pin "2") (pinfunction "2_2") (pintype "power_in"))
      (node (ref "P1") (pin "3") (pinfunction "3_3") (pintype "power_in"))
      (node (ref "PS1") (pin "1") (pinfunction "ADJ/GND_1") (pintype "passive"))
      (node (ref "R4") (pin "1") (pinfunction "1_1") (pintype "passive"))
      (node (ref "R5") (pin "1") (pinfunction "1_1") (pintype "passive"))
      (node (ref "R6") (pin "1") (pinfunction "1_1") (pintype "passive"))
      (node (ref "SW3") (pin "3") (pinfunction "3_3") (pintype "passive"))
      (node (ref "SW3") (pin "4") (pinfunction "4_4") (pintype "passive"))
      (node (ref "TP1") (pin "2") (pinfunction "Gnd_2") (pintype "passive"))
      (node (ref "TP10") (pin "2") (pinfunction "Gnd_2") (pintype "passive"))
      (node (ref "TP2") (pin "2") (pinfunction "Gnd_2") (pintype "passive"))
      (node (ref "TP3") (pin "2") (pinfunction "Gnd_2") (pintype "passive"))
      (node (ref "TP4") (pin "2") (pinfunction "Gnd_2") (pintype "passive"))
      (node (ref "TP5") (pin "2") (pinfunction "Gnd_2") (pintype "passive"))
      (node (ref "TP6") (pin "2") (pinfunction "Gnd_2") (pintype "passive"))
      (node (ref "TP7") (pin "2") (pinfunction "Gnd_2") (pintype "passive"))
      (node (ref "TP8") (pin "2") (pinfunction "Gnd_2") (pintype "passive"))
      (node (ref "TP9") (pin "2") (pinfunction "Gnd_2") (pintype "passive"))
      (node (ref "U1") (pin "21") (pinfunction "GND_21") (pintype "power_in"))
      (node (ref "U1") (pin "5") (pinfunction "GND_5") (pintype "power_in"))
      (node (ref "U2") (pin "1") (pinfunction "GND_1") (pintype "passive"))
      (node (ref "Y1") (pin "2") (pinfunction "GND_2") (pintype "passive"))
      (node (ref "Y1") (pin "4") (pinfunction "GND_4") (pintype "passive"))
      (node (ref "Y2") (pin "2") (pinfunction "GND_2") (pintype "passive"))
      (node (ref "Y2") (pin "4") (pinfunction "GND_4") (pintype "passive"))
    )
    (net (code "40") (name "Net-(LED1-Pad2)") (class "Default")
      (node (ref "LED1") (pin "2") (pinfunction "2_2") (pintype "passive"))
      (node (ref "R4") (pin "2") (pinfunction "2_2") (pintype "passive"))
    )
    (net (code "41") (name "Net-(LED2-Pad2)") (class "Default")
      (node (ref "LED2") (pin "2") (pinfunction "2_2") (pintype "passive"))
      (node (ref "R5") (pin "2") (pinfunction "2_2") (pintype "passive"))
    )
    (net (code "42") (name "Net-(LED3-Pad2)") (class "Default")
      (node (ref "LED3") (pin "2") (pinfunction "2_2") (pintype "passive"))
      (node (ref "R6") (pin "2") (pinfunction "2_2") (pintype "passive"))
    )
    (net (code "43") (name "Net-(LED4-Pad2)") (class "Default")
      (node (ref "LED4") (pin "2") (pinfunction "2_2") (pintype "passive"))
      (node (ref "R10") (pin "2") (pinfunction "2_2") (pintype "passive"))
    )
    (net (code "44") (name "Net-(LED5-Pad2)") (class "Default")
      (node (ref "LED5") (pin "2") (pinfunction "2_2") (pintype "passive"))
      (node (ref "R11") (pin "2") (pinfunction "2_2") (pintype "passive"))
    )
    (net (code "45") (name "Net-(U2-V3)") (class "Default")
      (node (ref "C14") (pin "2") (pinfunction "2_2") (pintype "passive"))
      (node (ref "U2") (pin "4") (pinfunction "V3_4") (pintype "passive"))
    )
    (net (code "46") (name "unconnected-(D1-IO-3-Pad4)") (class "Default")
      (node (ref "D1") (pin "4") (pinfunction "IO-3_4") (pintype "passive"))
    )
    (net (code "47") (name "unconnected-(D1-IO-4-Pad6)") (class "Default")
      (node (ref "D1") (pin "6") (pinfunction "IO-4_6") (pintype "passive"))
    )
    (net (code "48") (name "unconnected-(J2-ID-Pad4)") (class "Default")
      (node (ref "J2") (pin "4") (pinfunction "ID_4") (pintype "passive"))
    )
    (net (code "49") (name "unconnected-(J4-NC-Pad1)") (class "Default")
      (node (ref "J4") (pin "1") (pinfunction "NC_1") (pintype "passive"))
    )
    (net (code "50") (name "unconnected-(U1-ADC6-Pad19)") (class "Default")
      (node (ref "U1") (pin "19") (pinfunction "ADC6_19") (pintype "bidirectional"))
    )
    (net (code "51") (name "unconnected-(U1-ADC7-Pad22)") (class "Default")
      (node (ref "U1") (pin "22") (pinfunction "ADC7_22") (pintype "bidirectional"))
    )
    (net (code "52") (name "unconnected-(U1-GND-Pad3)") (class "Default")
      (node (ref "U1") (pin "3") (pinfunction "GND_3") (pintype "power_in"))
    )
    (net (code "53") (name "unconnected-(U2-CTS#-Pad9)") (class "Default")
      (node (ref "U2") (pin "9") (pinfunction "CTS#_9") (pintype "passive"))
    )
    (net (code "54") (name "unconnected-(U2-DCD#-Pad12)") (class "Default")
      (node (ref "U2") (pin "12") (pinfunction "DCD#_12") (pintype "passive"))
    )
    (net (code "55") (name "unconnected-(U2-DSR#-Pad10)") (class "Default")
      (node (ref "U2") (pin "10") (pinfunction "DSR#_10") (pintype "passive"))
    )
    (net (code "56") (name "unconnected-(U2-RI#-Pad11)") (class "Default")
      (node (ref "U2") (pin "11") (pinfunction "RI#_11") (pintype "passive"))
    )
    (net (code "57") (name "unconnected-(U2-RS232-Pad15)") (class "Default")
      (node (ref "U2") (pin "15") (pinfunction "RS232_15") (pintype "passive"))
    )
    (net (code "58") (name "unconnected-(U2-RTS#-Pad14)") (class "Default")
      (node (ref "U2") (pin "14") (pinfunction "RTS#_14") (pintype "passive"))
    )
  )
)
